# PD_receiver.net
KiCad netlist of a schematic drawn in Altium Designer
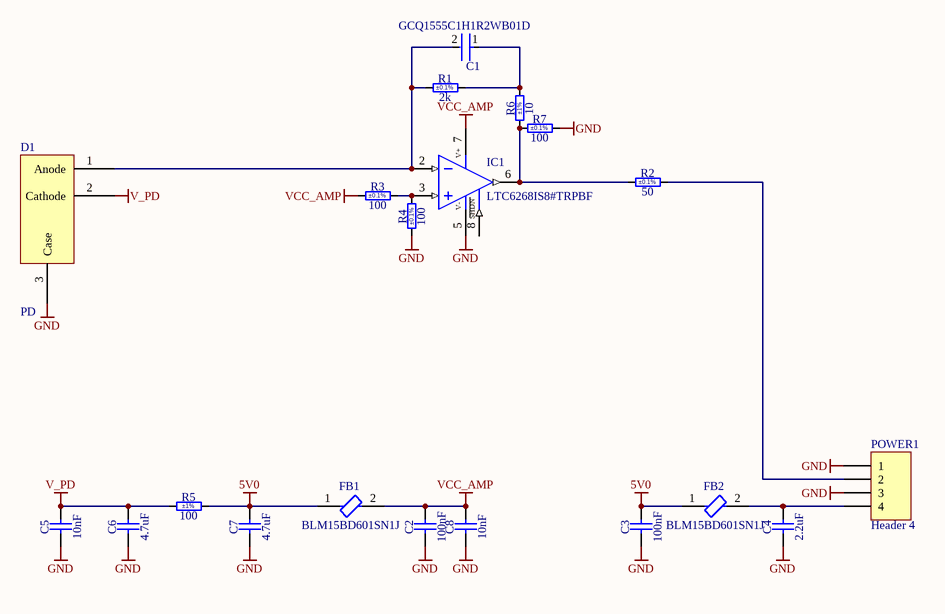
[diagram p0: PD_receiver.SchDoc]

(export (version "E")
  (design (tool "Eeschema 10.0.6"))
  (components
    (comp (ref "C1")
      (value "GCQ1555C1H1R2WB01D")
      (footprint "FP-GCQ155-0_05-IPC_B")
      (description "High Q Ceramic Capacitor for Automotive 1.2pF ±0.05pF 50VDC C0G 0402 Paper T/R")
      (libsource (lib "Altium Content Vault") (part "02cd4be3c70576c341d710602a673aa"))
    )
    (comp (ref "C2")
      (value "100nF")
      (footprint "CAPC1005X55N")
      (description "Non-polarised capacitor")
      (fields
        (field (name "PART NUMBER") "CC0402_100NF_16V_10%_X5R")
        (field (name "VOLTAGE") "16V")
        (field (name "AUTHOR") "CERN DEM JLC")
      )
      (libsource (lib "Capacitors") (part "Capacitor - non polarized"))
    )
    (comp (ref "C3")
      (value "100nF")
      (footprint "CAPC1005X55N")
      (description "Non-polarised capacitor")
      (fields
        (field (name "PART NUMBER") "CC0402_100NF_16V_10%_X5R")
        (field (name "VOLTAGE") "16V")
        (field (name "AUTHOR") "CERN DEM JLC")
      )
      (libsource (lib "Capacitors") (part "Capacitor - non polarized"))
    )
    (comp (ref "C4")
      (value "2.2uF")
      (footprint "CAPC1608X90N")
      (description "Non-polarised capacitor")
      (fields
        (field (name "PART NUMBER") "CC0603_2.2UF_10V_20%_X7R")
        (field (name "VOLTAGE") "10V")
        (field (name "AUTHOR") "CERN DEM JLC")
      )
      (libsource (lib "Capacitors") (part "Capacitor - non polarized"))
    )
    (comp (ref "C5")
      (value "10nF")
      (footprint "CAPC1005X55N")
      (description "Non-polarised capacitor")
      (fields
        (field (name "PART NUMBER") "CC0402_10NF_16V_10%_X7R")
        (field (name "VOLTAGE") "16V")
        (field (name "AUTHOR") "CERN DEM JLC")
      )
      (libsource (lib "Capacitors") (part "Capacitor - non polarized"))
    )
    (comp (ref "C6")
      (value "4.7uF")
      (footprint "CAPC1709X95N")
      (description "Non-polarised capacitor")
      (fields
        (field (name "PART NUMBER") "CC0603_4.7UF_16V_10%_X5R")
        (field (name "VOLTAGE") "16V")
        (field (name "AUTHOR") "CERN DEM JLC")
      )
      (libsource (lib "Capacitors") (part "Capacitor - non polarized"))
    )
    (comp (ref "C7")
      (value "4.7uF")
      (footprint "CAPC1709X95N")
      (description "Non-polarised capacitor")
      (fields
        (field (name "PART NUMBER") "CC0603_4.7UF_16V_10%_X5R")
        (field (name "VOLTAGE") "16V")
        (field (name "AUTHOR") "CERN DEM JLC")
      )
      (libsource (lib "Capacitors") (part "Capacitor - non polarized"))
    )
    (comp (ref "C8")
      (value "10nF")
      (footprint "CAPC1005X55N")
      (description "Non-polarised capacitor")
      (fields
        (field (name "PART NUMBER") "CC0402_10NF_16V_10%_X7R")
        (field (name "VOLTAGE") "16V")
        (field (name "AUTHOR") "CERN DEM JLC")
      )
      (libsource (lib "Capacitors") (part "Capacitor - non polarized"))
    )
    (comp (ref "D1")
      (value "PD")
      (footprint "PD_FTP_BM1")
      (description "Photodiode")
      (libsource (lib "Amplifier_Lib") (part "PD"))
    )
    (comp (ref "FB1")
      (value "BLM15BD601SN1J")
      (footprint "FP-BLM15-0_05-IPC_B")
      (description "Chip Ferrite Bead, 0402, 600Ω @ 100MHz, 0.65Ω, 25%, 200mA")
      (fields (field (name "TOLERANCE") "25%"))
      (libsource (lib "Altium Content Vault") (part "5f30dd21d616792df468990f7003faa"))
    )
    (comp (ref "FB2")
      (value "BLM15BD601SN1J")
      (footprint "FP-BLM15-0_05-IPC_B")
      (description "Chip Ferrite Bead, 0402, 600Ω @ 100MHz, 0.65Ω, 25%, 200mA")
      (fields (field (name "TOLERANCE") "25%"))
      (libsource (lib "Altium Content Vault") (part "5f30dd21d616792df468990f7003faa"))
    )
    (comp (ref "IC1")
      (value "LTC6268IS8#TRPBF")
      (footprint "SOIC127P600X175-8N")
      (description "500MHz Ultra-Low Bias Current FET Input Operational Amplifier")
      (fields (field (name "MANUFACTURER") "LINEAR TECHNOLOGY") (field (name "AUTHOR") "CERN DEM JLC"))
      (libsource (lib "ICs And Semiconductors") (part "LTC6268IS8"))
    )
    (comp (ref "POWER1")
      (value "Header 4")
      (footprint "HDR1X4")
      (description "Header, 4-Pin")
      (fields (field (name "PUBLISHER") "Altium Limited"))
      (libsource (lib "Miscellaneous Connectors") (part "Header 4"))
    )
    (comp (ref "R1")
      (value "2k")
      (footprint "RESC1608X55N")
      (description "Resistor - 0.1%")
      (fields
        (field (name "TOLERANCE") "±0.1%")
        (field (name "PART NUMBER") "R0603_2K_0.1%_0.063W_10PPM")
        (field (name "POWER") "0.063W")
        (field (name "AUTHOR") "CERN DEM JLC")
      )
      (libsource (lib "Resistors") (part "Resistor - 0.1%"))
    )
    (comp (ref "R2")
      (value "50")
      (footprint "RESC1005X35N")
      (description "Resistor - 0.1%")
      (fields
        (field (name "TOLERANCE") "±0.1%")
        (field (name "PART NUMBER") "R0402_50R_0.1%_0.05W_25PPM")
        (field (name "POWER") "0.05W")
        (field (name "AUTHOR") "CERN DEM JMW")
      )
      (libsource (lib "Resistors") (part "Resistor - 0.1%"))
    )
    (comp (ref "R3")
      (value "100")
      (footprint "RESC1005X35N")
      (description "Resistor - 0.1%")
      (fields
        (field (name "TOLERANCE") "±0.1%")
        (field (name "PART NUMBER") "R0402_100R_0.1%_0.063W_25PPM")
        (field (name "POWER") "0.063W")
        (field (name "AUTHOR") "CERN DEM JMW")
      )
      (libsource (lib "Resistors") (part "Resistor - 0.1%"))
    )
    (comp (ref "R4")
      (value "100")
      (footprint "RESC1005X35N")
      (description "Resistor - 0.1%")
      (fields
        (field (name "TOLERANCE") "±0.1%")
        (field (name "PART NUMBER") "R0402_100R_0.1%_0.063W_25PPM")
        (field (name "POWER") "0.063W")
        (field (name "AUTHOR") "CERN DEM JMW")
      )
      (libsource (lib "Resistors") (part "Resistor - 0.1%"))
    )
    (comp (ref "R5")
      (value "100")
      (footprint "RESC1005X40N")
      (description "Resistor - 1%")
      (fields
        (field (name "TOLERANCE") "±1%")
        (field (name "PART NUMBER") "R0402_100R_1%_0.0625W_100PPM")
        (field (name "POWER") "0.0625W")
        (field (name "AUTHOR") "CERN DEM JLC")
      )
      (libsource (lib "Resistors") (part "Resistor - 1%"))
    )
    (comp (ref "R6")
      (value "10")
      (footprint "RESC1005X40N")
      (description "Resistor - 1%")
      (fields
        (field (name "TOLERANCE") "±1%")
        (field (name "PART NUMBER") "R0402_10R_1%_0.0625W_200PPM")
        (field (name "POWER") "0.0625W")
        (field (name "AUTHOR") "CERN DEM JLC")
      )
      (libsource (lib "Resistors") (part "Resistor - 1%"))
    )
    (comp (ref "R7")
      (value "100")
      (footprint "RESC1005X35N")
      (description "Resistor - 0.1%")
      (fields
        (field (name "TOLERANCE") "±0.1%")
        (field (name "PART NUMBER") "R0402_100R_0.1%_0.063W_25PPM")
        (field (name "POWER") "0.063W")
        (field (name "AUTHOR") "CERN DEM JMW")
      )
      (libsource (lib "Resistors") (part "Resistor - 0.1%"))
    )
  )
  (nets
    (net (code "1") (name "5V0") (class "Default")
      (node (ref "C3") (pin "2") (pinfunction "2_2") (pintype "passive"))
      (node (ref "C7") (pin "2") (pinfunction "2_2") (pintype "passive"))
      (node (ref "FB1") (pin "1") (pinfunction "1_1") (pintype "passive"))
      (node (ref "FB2") (pin "1") (pinfunction "1_1") (pintype "passive"))
      (node (ref "R5") (pin "2") (pinfunction "2_2") (pintype "passive"))
    )
    (net (code "2") (name "GND") (class "Default")
      (node (ref "C2") (pin "1") (pinfunction "1_1") (pintype "passive"))
      (node (ref "C3") (pin "1") (pinfunction "1_1") (pintype "passive"))
      (node (ref "C4") (pin "1") (pinfunction "1_1") (pintype "passive"))
      (node (ref "C5") (pin "1") (pinfunction "1_1") (pintype "passive"))
      (node (ref "C6") (pin "1") (pinfunction "1_1") (pintype "passive"))
      (node (ref "C7") (pin "1") (pinfunction "1_1") (pintype "passive"))
      (node (ref "C8") (pin "1") (pinfunction "1_1") (pintype "passive"))
      (node (ref "D1") (pin "3") (pinfunction "Case_3") (pintype "passive"))
      (node (ref "IC1") (pin "5") (pinfunction "V-_5") (pintype "power_in"))
      (node (ref "POWER1") (pin "1") (pinfunction "1_1") (pintype "passive"))
      (node (ref "POWER1") (pin "3") (pinfunction "3_3") (pintype "passive"))
      (node (ref "R4") (pin "1") (pinfunction "1_1") (pintype "passive"))
      (node (ref "R7") (pin "2") (pinfunction "2_2") (pintype "passive"))
    )
    (net (code "3") (name "Net-(C1-Pad1)") (class "Default")
      (node (ref "C1") (pin "1") (pinfunction "1_1") (pintype "passive"))
      (node (ref "R1") (pin "2") (pinfunction "2_2") (pintype "passive"))
      (node (ref "R6") (pin "2") (pinfunction "2_2") (pintype "passive"))
    )
    (net (code "4") (name "Net-(C4-Pad2)") (class "Default")
      (node (ref "C4") (pin "2") (pinfunction "2_2") (pintype "passive"))
      (node (ref "FB2") (pin "2") (pinfunction "2_2") (pintype "passive"))
      (node (ref "POWER1") (pin "4") (pinfunction "4_4") (pintype "passive"))
    )
    (net (code "5") (name "Net-(D1-Anode)") (class "Default")
      (node (ref "C1") (pin "2") (pinfunction "2_2") (pintype "passive"))
      (node (ref "D1") (pin "1") (pinfunction "Anode_1") (pintype "passive"))
      (node (ref "IC1") (pin "2") (pinfunction "IN-_2") (pintype "input"))
      (node (ref "R1") (pin "1") (pinfunction "1_1") (pintype "passive"))
    )
    (net (code "6") (name "Net-(IC1-IN+)") (class "Default")
      (node (ref "IC1") (pin "3") (pinfunction "IN+_3") (pintype "input"))
      (node (ref "R3") (pin "2") (pinfunction "2_2") (pintype "passive"))
      (node (ref "R4") (pin "2") (pinfunction "2_2") (pintype "passive"))
    )
    (net (code "7") (name "Net-(IC1-OUT)") (class "Default")
      (node (ref "IC1") (pin "6") (pinfunction "OUT_6") (pintype "output"))
      (node (ref "R2") (pin "1") (pinfunction "1_1") (pintype "passive"))
      (node (ref "R6") (pin "1") (pinfunction "1_1") (pintype "passive"))
      (node (ref "R7") (pin "1") (pinfunction "1_1") (pintype "passive"))
    )
    (net (code "8") (name "Net-(POWER1-Pad2)") (class "Default")
      (node (ref "POWER1") (pin "2") (pinfunction "2_2") (pintype "passive"))
      (node (ref "R2") (pin "2") (pinfunction "2_2") (pintype "passive"))
    )
    (net (code "9") (name "VCC_AMP") (class "Default")
      (node (ref "C2") (pin "2") (pinfunction "2_2") (pintype "passive"))
      (node (ref "C8") (pin "2") (pinfunction "2_2") (pintype "passive"))
      (node (ref "FB1") (pin "2") (pinfunction "2_2") (pintype "passive"))
      (node (ref "IC1") (pin "7") (pinfunction "VCC_7") (pintype "power_in"))
      (node (ref "R3") (pin "1") (pinfunction "1_1") (pintype "passive"))
    )
    (net (code "10") (name "V_PD") (class "Default")
      (node (ref "C5") (pin "2") (pinfunction "2_2") (pintype "passive"))
      (node (ref "C6") (pin "2") (pinfunction "2_2") (pintype "passive"))
      (node (ref "D1") (pin "2") (pinfunction "Cathode_2") (pintype "passive"))
      (node (ref "R5") (pin "1") (pinfunction "1_1") (pintype "passive"))
    )
    (net (code "11") (name "unconnected-(IC1-~{SHDN}-Pad8)") (class "Default")
      (node (ref "IC1") (pin "8") (pinfunction "~{SHDN}_8") (pintype "input"))
    )
  )
)
